# LTC3112_buck-boost.net
KiCad netlist of a schematic drawn in EAGLE
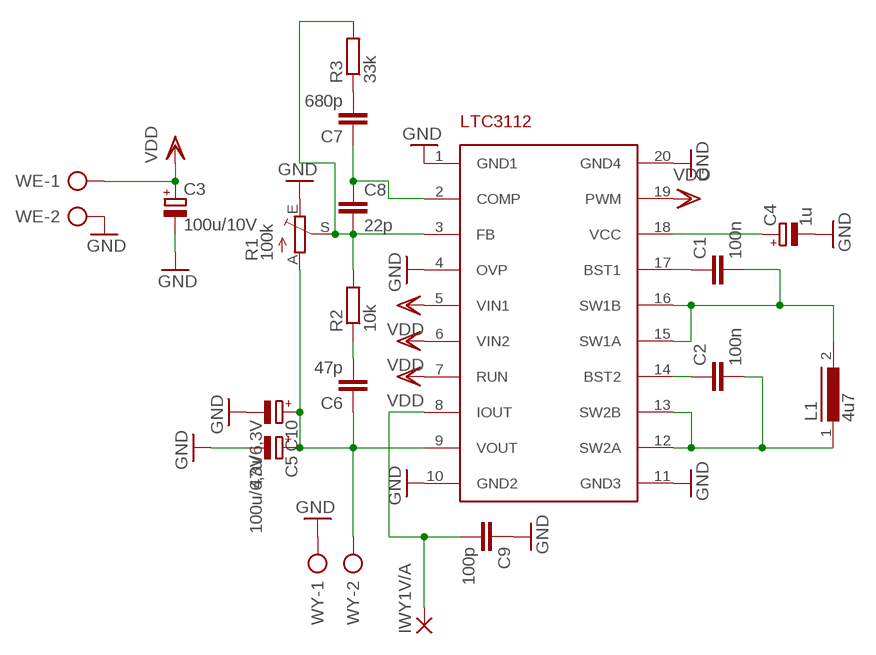
[diagram p0: schematic, sheet 1]

(export (version "E")
  (design (tool "Eeschema 10.0.6"))
  (components
    (comp (ref "C1")
      (value "100n")
      (footprint "eagle-import:C0603K")
      (libsource (lib "eagle-import") (part "C-EUC0603K"))
    )
    (comp (ref "C2")
      (value "100n")
      (footprint "eagle-import:C0603K")
      (libsource (lib "eagle-import") (part "C-EUC0603K"))
    )
    (comp (ref "C3")
      (value "100u/10V")
      (footprint "eagle-import:E2,5-6")
      (libsource (lib "eagle-import") (part "CPOL-EUE2.5-6"))
    )
    (comp (ref "C4")
      (value "1u")
      (footprint "eagle-import:SMC_B")
      (libsource (lib "eagle-import") (part "CPOL-EUSMCB"))
    )
    (comp (ref "C5")
      (value "100u/6,3V")
      (footprint "eagle-import:E2,5-7")
      (libsource (lib "eagle-import") (part "CPOL-EUE2.5-7"))
    )
    (comp (ref "C6")
      (value "47p")
      (footprint "eagle-import:C0805")
      (libsource (lib "eagle-import") (part "C-EUC0805"))
    )
    (comp (ref "C7")
      (value "680p")
      (footprint "eagle-import:C0805")
      (libsource (lib "eagle-import") (part "C-EUC0805"))
    )
    (comp (ref "C8")
      (value "22p")
      (footprint "eagle-import:C0805")
      (libsource (lib "eagle-import") (part "C-EUC0805"))
    )
    (comp (ref "C9")
      (value "100p")
      (footprint "eagle-import:C0805")
      (libsource (lib "eagle-import") (part "C-EUC0805"))
    )
    (comp (ref "C10")
      (value "47u/6,3V")
      (footprint "eagle-import:E1,8-4")
      (libsource (lib "eagle-import") (part "CPOL-EUE1.8-4"))
    )
    (comp (ref "IWY1V/A")
      (value "1,6/0,8")
      (footprint "eagle-import:1,6_0,8")
      (libsource (lib "eagle-import") (part "1,6/0,8"))
    )
    (comp (ref "L1")
      (value "4u7")
      (footprint "eagle-import:DR73")
      (libsource (lib "eagle-import") (part "DR73"))
    )
    (comp (ref "R1")
      (value "100k")
      (footprint "eagle-import:RJ9W")
      (libsource (lib "eagle-import") (part "TRIM_EU-RJ9W"))
    )
    (comp (ref "R2")
      (value "10k")
      (footprint "eagle-import:R0805")
      (libsource (lib "eagle-import") (part "R-EU_R0805"))
    )
    (comp (ref "R3")
      (value "33k")
      (footprint "eagle-import:R0805")
      (libsource (lib "eagle-import") (part "R-EU_R0805"))
    )
    (comp (ref "U$1")
      (value "LTC3112")
      (footprint "eagle-import:TSSOP20")
      (libsource (lib "eagle-import") (part "LTC3112"))
    )
    (comp (ref "WE")
      (value "AK300/2")
      (footprint "eagle-import:AK300_2")
      (libsource (lib "eagle-import") (part "AK300/2"))
    )
    (comp (ref "WY")
      (value "AK300/2")
      (footprint "eagle-import:AK300_2")
      (libsource (lib "eagle-import") (part "AK300/2"))
    )
  )
  (nets
    (net (code "1") (name "GND") (class "Default")
      (node (ref "C10") (pin "-") (pinfunction "-_-") (pintype "passive"))
      (node (ref "C3") (pin "-") (pinfunction "-_-") (pintype "passive"))
      (node (ref "C4") (pin "-") (pinfunction "-_-") (pintype "passive"))
      (node (ref "C5") (pin "-") (pinfunction "-_-") (pintype "passive"))
      (node (ref "C9") (pin "1") (pinfunction "1_1") (pintype "passive"))
      (node (ref "R1") (pin "E") (pinfunction "E_E") (pintype "passive"))
      (node (ref "U$1") (pin "1") (pinfunction "GND1_1") (pintype "bidirectional"))
      (node (ref "U$1") (pin "10") (pinfunction "GND2_10") (pintype "bidirectional"))
      (node (ref "U$1") (pin "11") (pinfunction "GND3_11") (pintype "bidirectional"))
      (node (ref "U$1") (pin "20") (pinfunction "GND4_20") (pintype "bidirectional"))
      (node (ref "U$1") (pin "4") (pinfunction "OVP_4") (pintype "bidirectional"))
      (node (ref "WE") (pin "2") (pinfunction "KL_2") (pintype "passive"))
      (node (ref "WY") (pin "1") (pinfunction "KL_1") (pintype "passive"))
    )
    (net (code "2") (name "Net-(C6-Pad2)") (class "Default")
      (node (ref "C6") (pin "2") (pinfunction "2_2") (pintype "passive"))
      (node (ref "R2") (pin "1") (pinfunction "1_1") (pintype "passive"))
    )
    (net (code "3") (name "Net-(C7-Pad2)") (class "Default")
      (node (ref "C7") (pin "2") (pinfunction "2_2") (pintype "passive"))
      (node (ref "R3") (pin "1") (pinfunction "1_1") (pintype "passive"))
    )
    (net (code "4") (name "Net-(IWY1V/A-P)") (class "Default")
      (node (ref "C9") (pin "2") (pinfunction "2_2") (pintype "passive"))
      (node (ref "IWY1V/A") (pin "1") (pinfunction "P_1") (pintype "passive"))
      (node (ref "U$1") (pin "8") (pinfunction "IOUT_8") (pintype "bidirectional"))
    )
    (net (code "5") (name "Net-(U$1-BST1)") (class "Default")
      (node (ref "C1") (pin "1") (pinfunction "1_1") (pintype "passive"))
      (node (ref "U$1") (pin "17") (pinfunction "BST1_17") (pintype "bidirectional"))
    )
    (net (code "6") (name "Net-(U$1-BST2)") (class "Default")
      (node (ref "C2") (pin "1") (pinfunction "1_1") (pintype "passive"))
      (node (ref "U$1") (pin "14") (pinfunction "BST2_14") (pintype "bidirectional"))
    )
    (net (code "7") (name "Net-(U$1-COMP)") (class "Default")
      (node (ref "C7") (pin "1") (pinfunction "1_1") (pintype "passive"))
      (node (ref "C8") (pin "1") (pinfunction "1_1") (pintype "passive"))
      (node (ref "U$1") (pin "2") (pinfunction "COMP_2") (pintype "bidirectional"))
    )
    (net (code "8") (name "Net-(U$1-FB)") (class "Default")
      (node (ref "C8") (pin "2") (pinfunction "2_2") (pintype "passive"))
      (node (ref "R1") (pin "S") (pinfunction "S_S") (pintype "passive"))
      (node (ref "R2") (pin "2") (pinfunction "2_2") (pintype "passive"))
      (node (ref "R3") (pin "2") (pinfunction "2_2") (pintype "passive"))
      (node (ref "U$1") (pin "3") (pinfunction "FB_3") (pintype "bidirectional"))
    )
    (net (code "9") (name "Net-(U$1-SW1A)") (class "Default")
      (node (ref "C1") (pin "2") (pinfunction "2_2") (pintype "passive"))
      (node (ref "L1") (pin "2") (pinfunction "2_2") (pintype "passive"))
      (node (ref "U$1") (pin "15") (pinfunction "SW1A_15") (pintype "bidirectional"))
      (node (ref "U$1") (pin "16") (pinfunction "SW1B_16") (pintype "bidirectional"))
    )
    (net (code "10") (name "Net-(U$1-SW2A)") (class "Default")
      (node (ref "C2") (pin "2") (pinfunction "2_2") (pintype "passive"))
      (node (ref "L1") (pin "1") (pinfunction "1_1") (pintype "passive"))
      (node (ref "U$1") (pin "12") (pinfunction "SW2A_12") (pintype "bidirectional"))
      (node (ref "U$1") (pin "13") (pinfunction "SW2B_13") (pintype "bidirectional"))
    )
    (net (code "11") (name "Net-(U$1-VCC)") (class "Default")
      (node (ref "C4") (pin "+") (pinfunction "+_+") (pintype "passive"))
      (node (ref "U$1") (pin "18") (pinfunction "VCC_18") (pintype "bidirectional"))
    )
    (net (code "12") (name "Net-(U$1-VOUT)") (class "Default")
      (node (ref "C10") (pin "+") (pinfunction "+_+") (pintype "passive"))
      (node (ref "C5") (pin "+") (pinfunction "+_+") (pintype "passive"))
      (node (ref "C6") (pin "1") (pinfunction "1_1") (pintype "passive"))
      (node (ref "R1") (pin "A") (pinfunction "A_A") (pintype "passive"))
      (node (ref "U$1") (pin "9") (pinfunction "VOUT_9") (pintype "bidirectional"))
      (node (ref "WY") (pin "2") (pinfunction "KL_2") (pintype "passive"))
    )
    (net (code "13") (name "VDD") (class "Default")
      (node (ref "C3") (pin "+") (pinfunction "+_+") (pintype "passive"))
      (node (ref "U$1") (pin "19") (pinfunction "PWM_19") (pintype "bidirectional"))
      (node (ref "U$1") (pin "5") (pinfunction "VIN1_5") (pintype "bidirectional"))
      (node (ref "U$1") (pin "6") (pinfunction "VIN2_6") (pintype "bidirectional"))
      (node (ref "U$1") (pin "7") (pinfunction "RUN_7") (pintype "bidirectional"))
      (node (ref "WE") (pin "1") (pinfunction "KL_1") (pintype "passive"))
    )
  )
)
